# RedBoard_Plus.net
KiCad netlist of a schematic drawn in EAGLE
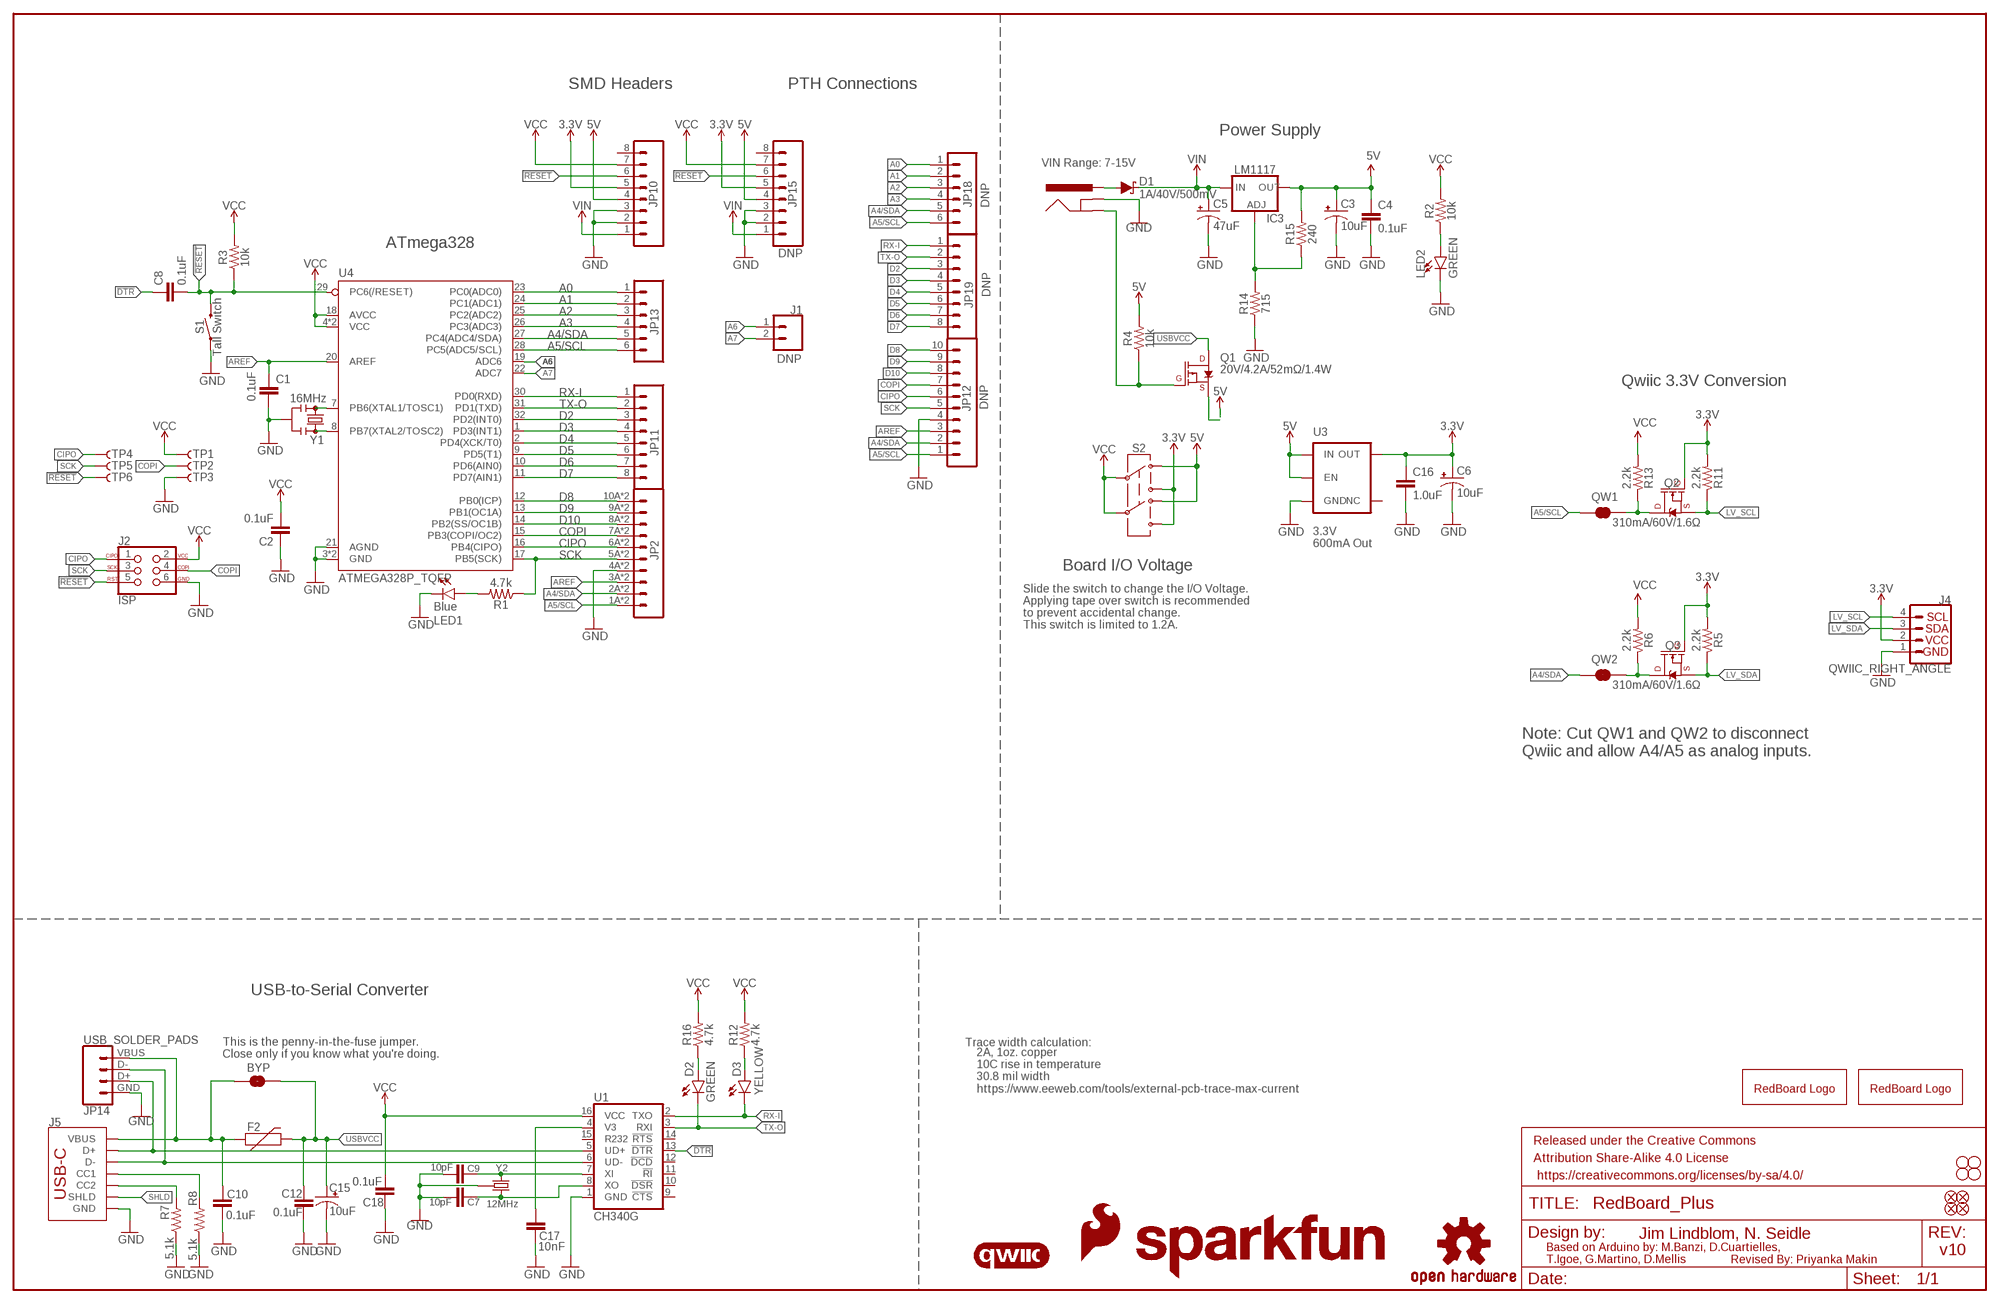
[diagram p0: schematic, sheet 1]

(export (version "E")
  (design (tool "Eeschema 10.0.6"))
  (components
    (comp (ref "BYP")
      (value "JUMPER-SMT_2_NO_SILK")
      (footprint "eagle-import:SMT-JUMPER_2_NO_SILK")
      (libsource (lib "eagle-import") (part "JUMPER-SMT_2_NO_SILK"))
    )
    (comp (ref "C1")
      (value "0.1uF")
      (footprint "eagle-import:0603")
      (libsource (lib "eagle-import") (part "0.1UF-0603-25V-(+80/-20%)"))
    )
    (comp (ref "C2")
      (value "0.1uF")
      (footprint "eagle-import:0603")
      (libsource (lib "eagle-import") (part "0.1UF-0603-25V-(+80/-20%)"))
    )
    (comp (ref "C3")
      (value "10uF")
      (footprint "eagle-import:EIA3216")
      (libsource (lib "eagle-import") (part "10UF-POLAR-EIA3216-16V-10%(TANT)"))
    )
    (comp (ref "C4")
      (value "0.1uF")
      (footprint "eagle-import:0603")
      (libsource (lib "eagle-import") (part "0.1UF-0603-25V-(+80/-20%)"))
    )
    (comp (ref "C5")
      (value "47uF")
      (footprint "eagle-import:PANASONIC_D")
      (libsource (lib "eagle-import") (part "47UF-POLAR-PANASONIC_D-35V-20%"))
    )
    (comp (ref "C6")
      (value "10uF")
      (footprint "eagle-import:EIA3216")
      (libsource (lib "eagle-import") (part "10UF-POLAR-EIA3216-16V-10%(TANT)"))
    )
    (comp (ref "C7")
      (value "10pF")
      (footprint "eagle-import:0603")
      (libsource (lib "eagle-import") (part "10PF-0603-50V-5%"))
    )
    (comp (ref "C8")
      (value "0.1uF")
      (footprint "eagle-import:0603")
      (libsource (lib "eagle-import") (part "0.1UF-0603-25V-(+80/-20%)"))
    )
    (comp (ref "C9")
      (value "10pF")
      (footprint "eagle-import:0603")
      (libsource (lib "eagle-import") (part "10PF-0603-50V-5%"))
    )
    (comp (ref "C10")
      (value "0.1uF")
      (footprint "eagle-import:0603")
      (libsource (lib "eagle-import") (part "0.1UF-0603-25V-(+80/-20%)"))
    )
    (comp (ref "C12")
      (value "0.1uF")
      (footprint "eagle-import:0603")
      (libsource (lib "eagle-import") (part "0.1UF-0603-25V-(+80/-20%)"))
    )
    (comp (ref "C15")
      (value "10uF")
      (footprint "eagle-import:EIA3216")
      (libsource (lib "eagle-import") (part "10UF-POLAR-EIA3216-16V-10%(TANT)"))
    )
    (comp (ref "C16")
      (value "1.0uF")
      (footprint "eagle-import:0603")
      (libsource (lib "eagle-import") (part "1.0UF-0603-16V-10%"))
    )
    (comp (ref "C17")
      (value "10nF")
      (footprint "eagle-import:0603")
      (libsource (lib "eagle-import") (part "10NF-0603-50V-10%"))
    )
    (comp (ref "C18")
      (value "0.1uF")
      (footprint "eagle-import:0603")
      (libsource (lib "eagle-import") (part "0.1UF-0603-25V-(+80/-20%)"))
    )
    (comp (ref "D1")
      (value "1A/40V/500mV")
      (footprint "eagle-import:SMA-DIODE")
      (libsource (lib "eagle-import") (part "DIODE-SCHOTTKY-SS14"))
    )
    (comp (ref "D2")
      (value "GREEN")
      (footprint "eagle-import:LED-1206")
      (libsource (lib "eagle-import") (part "LED-GREENLILYPAD"))
    )
    (comp (ref "D3")
      (value "YELLOW")
      (footprint "eagle-import:LED-1206-HIDDENSILK")
      (libsource (lib "eagle-import") (part "LED-YELLOW_HIDDENSILK"))
    )
    (comp (ref "F2")
      (value "6V/2A")
      (footprint "eagle-import:1210")
      (libsource (lib "eagle-import") (part "PPTC_6V2A"))
    )
    (comp (ref "FD1")
      (value "FIDUCIAL1X2")
      (footprint "eagle-import:FIDUCIAL-1X2")
      (libsource (lib "eagle-import") (part "FIDUCIAL1X2"))
    )
    (comp (ref "FD2")
      (value "FIDUCIAL1X2")
      (footprint "eagle-import:FIDUCIAL-1X2")
      (libsource (lib "eagle-import") (part "FIDUCIAL1X2"))
    )
    (comp (ref "FRAME1")
      (value "FRAME-LEDGER")
      (footprint "eagle-import:CREATIVE_COMMONS")
      (libsource (lib "eagle-import") (part "FRAME-LEDGER"))
    )
    (comp (ref "IC3")
      (value "LM1117")
      (footprint "eagle-import:SOT223")
      (fields (field (name "PROD_ID") "VREG-08170"))
      (libsource (lib "eagle-import") (part "V_REG_LM1117SOT223"))
    )
    (comp (ref "J1")
      (value "DNP")
      (footprint "eagle-import:1X02_NO_SILK")
      (libsource (lib "eagle-import") (part "CONN_021X02_NO_SILK"))
    )
    (comp (ref "J2")
      (value "ISP")
      (footprint "eagle-import:2X3_SMT_POSTS")
      (libsource (lib "eagle-import") (part "AVR_SPI_PROG_3X2SMD"))
    )
    (comp (ref "J3")
      (value "5.5x2.1mm Barrel")
      (footprint "eagle-import:POWER_JACK_SMD")
      (fields (field (name "PROD_ID") "CONN-08106"))
      (libsource (lib "eagle-import") (part "POWER_JACKSMD"))
    )
    (comp (ref "J4")
      (value "QWIIC_RIGHT_ANGLE")
      (footprint "eagle-import:JST04_1MM_RA")
      (libsource (lib "eagle-import") (part "QWIIC_CONNECTORJS-1MM"))
    )
    (comp (ref "J5")
      (value "USB Female Type C Connector")
      (footprint "eagle-import:USB-C-16P-2LAYER-PADS")
      (libsource (lib "eagle-import") (part "USB_C_2-LAYER_PADS"))
    )
    (comp (ref "JP1")
      (value "SFE_LOGO_NAME.1_INCH")
      (footprint "eagle-import:SFE_LOGO_NAME_.1")
      (libsource (lib "eagle-import") (part "SFE_LOGO_NAME.1_INCH"))
    )
    (comp (ref "JP2")
      (value "CONN_10SMD_COMBO-FEMALE")
      (footprint "eagle-import:1X10_SMD_COMBINED")
      (fields (field (name "PROD_ID") "CONN-11219"))
      (libsource (lib "eagle-import") (part "CONN_10SMD_COMBO-FEMALE"))
    )
    (comp (ref "JP3")
      (value "STAND-OFFTIGHT")
      (footprint "eagle-import:STAND-OFF-TIGHT")
      (libsource (lib "eagle-import") (part "STAND-OFFTIGHT"))
    )
    (comp (ref "JP4")
      (value "STAND-OFFTIGHT")
      (footprint "eagle-import:STAND-OFF-TIGHT")
      (libsource (lib "eagle-import") (part "STAND-OFFTIGHT"))
    )
    (comp (ref "JP5")
      (value "STAND-OFFTIGHT")
      (footprint "eagle-import:STAND-OFF-TIGHT")
      (libsource (lib "eagle-import") (part "STAND-OFFTIGHT"))
    )
    (comp (ref "JP6")
      (value "STAND-OFFTIGHT")
      (footprint "eagle-import:STAND-OFF-TIGHT")
      (libsource (lib "eagle-import") (part "STAND-OFFTIGHT"))
    )
    (comp (ref "JP7")
      (value "SFE_LOGO_FLAME.1_INCH")
      (footprint "eagle-import:SFE_LOGO_FLAME_.1")
      (libsource (lib "eagle-import") (part "SFE_LOGO_FLAME.1_INCH"))
    )
    (comp (ref "JP8")
      (value "FIDUCIAL1X2")
      (footprint "eagle-import:FIDUCIAL-1X2")
      (libsource (lib "eagle-import") (part "FIDUCIAL1X2"))
    )
    (comp (ref "JP9")
      (value "FIDUCIAL1X2")
      (footprint "eagle-import:FIDUCIAL-1X2")
      (libsource (lib "eagle-import") (part "FIDUCIAL1X2"))
    )
    (comp (ref "JP10")
      (value "CONN_08SMD-COMBO-FEMALE")
      (footprint "eagle-import:1X08_SMD_COMBINED")
      (fields (field (name "PROD_ID") "CONN-10204"))
      (libsource (lib "eagle-import") (part "CONN_08SMD-COMBO-FEMALE"))
    )
    (comp (ref "JP11")
      (value "JP11")
      (footprint "eagle-import:1X08_SMD_COMBINED")
      (fields (field (name "PROD_ID") "CONN-10204"))
      (libsource (lib "eagle-import") (part "CONN_08SMD-COMBO-FEMALE"))
    )
    (comp (ref "JP12")
      (value "DNP")
      (footprint "eagle-import:1X10_NO_SILK")
      (libsource (lib "eagle-import") (part "CONN_10NO_SILK_PTH_FEMALE"))
    )
    (comp (ref "JP13")
      (value "CONN_06SMD-STRAIGHT-COMBO-FEMALE")
      (footprint "eagle-import:1X06_SMD_STRAIGHT_COMBO")
      (fields (field (name "PROD_ID") "CONN-10203"))
      (libsource (lib "eagle-import") (part "CONN_06SMD-STRAIGHT-COMBO-FEMALE"))
    )
    (comp (ref "JP14")
      (value "USB_SOLDER_PADS")
      (footprint "eagle-import:USB-SOLDER-PADS")
      (libsource (lib "eagle-import") (part "USB_SOLDER_PADS"))
    )
    (comp (ref "JP15")
      (value "DNP")
      (footprint "eagle-import:1X08_NO_SILK")
      (libsource (lib "eagle-import") (part "CONN_08NO_SILK_DNP"))
    )
    (comp (ref "JP18")
      (value "DNP")
      (footprint "eagle-import:1X06_NO_SILK")
      (libsource (lib "eagle-import") (part "CONN_06NO_SILK_NO_POP"))
    )
    (comp (ref "JP19")
      (value "DNP")
      (footprint "eagle-import:1X08_NO_SILK")
      (libsource (lib "eagle-import") (part "CONN_08NO_SILK_DNP"))
    )
    (comp (ref "LED1")
      (value "Blue")
      (footprint "eagle-import:LED-1206-HIDDENSILK")
      (fields (field (name "PROD_ID") "DIO-09911"))
      (libsource (lib "eagle-import") (part "LED-BLUE_HIDDENSILK"))
    )
    (comp (ref "LED2")
      (value "GREEN")
      (footprint "eagle-import:LED-1206")
      (libsource (lib "eagle-import") (part "LED-GREENLILYPAD"))
    )
    (comp (ref "LOGO1")
      (value "QWIIC_LOGO_5MM")
      (footprint "eagle-import:QWIIC_5MM")
      (libsource (lib "eagle-import") (part "QWIIC_LOGO_5MM"))
    )
    (comp (ref "Q1")
      (value "20V/4.2A/52mΩ/1.4W")
      (footprint "eagle-import:SOT23-3")
      (libsource (lib "eagle-import") (part "MOSFET_PCH-DMG2305UX-7"))
    )
    (comp (ref "Q2")
      (value "310mA/60V/1.6Ω")
      (footprint "eagle-import:SOT323")
      (libsource (lib "eagle-import") (part "MOSFET-NCH-2N7002PW"))
    )
    (comp (ref "Q3")
      (value "310mA/60V/1.6Ω")
      (footprint "eagle-import:SOT323")
      (libsource (lib "eagle-import") (part "MOSFET-NCH-2N7002PW"))
    )
    (comp (ref "QW1")
      (value "JUMPER-SMT_2_NC_TRACE_SILK")
      (footprint "eagle-import:SMT-JUMPER_2_NC_TRACE_SILK")
      (libsource (lib "eagle-import") (part "JUMPER-SMT_2_NC_TRACE_SILK"))
    )
    (comp (ref "QW2")
      (value "JUMPER-SMT_2_NC_TRACE_SILK")
      (footprint "eagle-import:SMT-JUMPER_2_NC_TRACE_SILK")
      (libsource (lib "eagle-import") (part "JUMPER-SMT_2_NC_TRACE_SILK"))
    )
    (comp (ref "R1")
      (value "4.7k")
      (footprint "eagle-import:0603")
      (libsource (lib "eagle-import") (part "4.7KOHM-0603-1/10W-1%"))
    )
    (comp (ref "R2")
      (value "10k")
      (footprint "eagle-import:0603")
      (libsource (lib "eagle-import") (part "10KOHM-0603-1/10W-1%"))
    )
    (comp (ref "R3")
      (value "10k")
      (footprint "eagle-import:0603")
      (libsource (lib "eagle-import") (part "10KOHM-0603-1/10W-1%"))
    )
    (comp (ref "R4")
      (value "10k")
      (footprint "eagle-import:0603")
      (libsource (lib "eagle-import") (part "10KOHM-0603-1/10W-1%"))
    )
    (comp (ref "R5")
      (value "2.2k")
      (footprint "eagle-import:0603")
      (libsource (lib "eagle-import") (part "2.2KOHM-0603-1/10W-1%"))
    )
    (comp (ref "R6")
      (value "2.2k")
      (footprint "eagle-import:0603")
      (libsource (lib "eagle-import") (part "2.2KOHM-0603-1/10W-1%"))
    )
    (comp (ref "R7")
      (value "5.1k")
      (footprint "eagle-import:0603")
      (libsource (lib "eagle-import") (part "5.1KOHM5.1KOHM-0603-1/10W-1%"))
    )
    (comp (ref "R8")
      (value "5.1k")
      (footprint "eagle-import:0603")
      (libsource (lib "eagle-import") (part "5.1KOHM5.1KOHM-0603-1/10W-1%"))
    )
    (comp (ref "R11")
      (value "2.2k")
      (footprint "eagle-import:0603")
      (libsource (lib "eagle-import") (part "2.2KOHM-0603-1/10W-1%"))
    )
    (comp (ref "R12")
      (value "4.7k")
      (footprint "eagle-import:0603")
      (libsource (lib "eagle-import") (part "4.7KOHM-0603-1/10W-1%"))
    )
    (comp (ref "R13")
      (value "2.2k")
      (footprint "eagle-import:0603")
      (libsource (lib "eagle-import") (part "2.2KOHM-0603-1/10W-1%"))
    )
    (comp (ref "R14")
      (value "715")
      (footprint "eagle-import:0603")
      (libsource (lib "eagle-import") (part "715OHM-0603-1/10W-1%"))
    )
    (comp (ref "R15")
      (value "240")
      (footprint "eagle-import:0603")
      (libsource (lib "eagle-import") (part "240OHM-0603-1/10W-1%"))
    )
    (comp (ref "R16")
      (value "4.7k")
      (footprint "eagle-import:0603")
      (libsource (lib "eagle-import") (part "4.7KOHM-0603-1/10W-1%"))
    )
    (comp (ref "S1")
      (value "Tall Switch")
      (footprint "eagle-import:TACTILE_SWITCH_SMD_5.2MM")
      (libsource (lib "eagle-import") (part "MOMENTARY-SWITCH-SPST-SMD-5.2-TALL-REDUNDANT"))
    )
    (comp (ref "S2")
      (value "SWITCH-DPDT-SMD-AYZ0202")
      (footprint "eagle-import:SWITCH_DPDT_SMD_AYZ0202")
      (libsource (lib "eagle-import") (part "SWITCH-DPDT-SMD-AYZ0202"))
    )
    (comp (ref "TP1")
      (value "TP-3x5")
      (footprint "eagle-import:PAD.03X.05")
      (libsource (lib "eagle-import") (part "TEST-POINT3X5"))
    )
    (comp (ref "TP2")
      (value "TP-3x5")
      (footprint "eagle-import:PAD.03X.05")
      (libsource (lib "eagle-import") (part "TEST-POINT3X5"))
    )
    (comp (ref "TP3")
      (value "TP-3x5")
      (footprint "eagle-import:PAD.03X.05")
      (libsource (lib "eagle-import") (part "TEST-POINT3X5"))
    )
    (comp (ref "TP4")
      (value "TP-3x5")
      (footprint "eagle-import:PAD.03X.05")
      (libsource (lib "eagle-import") (part "TEST-POINT3X5"))
    )
    (comp (ref "TP5")
      (value "TP-3x5")
      (footprint "eagle-import:PAD.03X.05")
      (libsource (lib "eagle-import") (part "TEST-POINT3X5"))
    )
    (comp (ref "TP6")
      (value "TP-3x5")
      (footprint "eagle-import:PAD.03X.05")
      (libsource (lib "eagle-import") (part "TEST-POINT3X5"))
    )
    (comp (ref "U$1")
      (value "REDBOARD_LOGO")
      (footprint "eagle-import:REDBOARD_LOGO")
      (libsource (lib "eagle-import") (part "REDBOARD_LOGO"))
    )
    (comp (ref "U$3")
      (value "REDBOARD_LOGO")
      (footprint "eagle-import:REDBOARD_LOGO")
      (libsource (lib "eagle-import") (part "REDBOARD_LOGO"))
    )
    (comp (ref "U$16")
      (value "OSHW-LOGOS")
      (footprint "eagle-import:OSHW-LOGO-S")
      (libsource (lib "eagle-import") (part "OSHW-LOGOS"))
    )
    (comp (ref "U1")
      (value "CH340G")
      (footprint "eagle-import:SO016")
      (libsource (lib "eagle-import") (part "CH340GSMD"))
    )
    (comp (ref "U3")
      (value "3.3V")
      (footprint "eagle-import:SOT23-5")
      (libsource (lib "eagle-import") (part "V_REG_AP2112K-3.3V"))
    )
    (comp (ref "U4")
      (value "ATMEGA328P_TQFP")
      (footprint "eagle-import:TQFP32-08")
      (libsource (lib "eagle-import") (part "ATMEGA328P_TQFP"))
    )
    (comp (ref "Y1")
      (value "16MHz")
      (footprint "eagle-import:RESONATOR-SMD-3.2X1.3")
      (libsource (lib "eagle-import") (part "RESONATOR-16MHZSMD_3.2X1.3"))
    )
    (comp (ref "Y2")
      (value "12MHz")
      (footprint "eagle-import:CRYSTAL-SMD-3.2X2.5MM")
      (libsource (lib "eagle-import") (part "CRYSTAL-GROUNDEDSMD-3.2X2.5"))
    )
  )
  (nets
    (net (code "1") (name "/~{DTR}") (class "Default")
      (node (ref "C8") (pin "1") (pinfunction "1_1") (pintype "passive"))
      (node (ref "U1") (pin "13") (pinfunction "~{DTR}_13") (pintype "bidirectional"))
    )
    (net (code "2") (name "/~{RESET}") (class "Default")
      (node (ref "C8") (pin "2") (pinfunction "2_2") (pintype "passive"))
      (node (ref "J2") (pin "5") (pinfunction "5_5") (pintype "passive"))
      (node (ref "JP10") (pin "6") (pinfunction "6_6") (pintype "passive"))
      (node (ref "JP15") (pin "6") (pinfunction "6_6") (pintype "passive"))
      (node (ref "R3") (pin "1") (pinfunction "1_1") (pintype "passive"))
      (node (ref "S1") (pin "3") (pinfunction "2_3") (pintype "passive"))
      (node (ref "S1") (pin "4") (pinfunction "2_4") (pintype "passive"))
      (node (ref "TP6") (pin "P$1") (pinfunction "1_P$1") (pintype "bidirectional"))
      (node (ref "U4") (pin "29") (pinfunction "PC6(/RESET)_29") (pintype "bidirectional"))
    )
    (net (code "3") (name "3.3V") (class "Default")
      (node (ref "C16") (pin "1") (pinfunction "1_1") (pintype "passive"))
      (node (ref "C6") (pin "+") (pinfunction "+_+") (pintype "passive"))
      (node (ref "J4") (pin "2") (pinfunction "2_2") (pintype "power_in"))
      (node (ref "JP10") (pin "5") (pinfunction "5_5") (pintype "passive"))
      (node (ref "JP15") (pin "5") (pinfunction "5_5") (pintype "passive"))
      (node (ref "Q2") (pin "1") (pinfunction "G_1") (pintype "bidirectional"))
      (node (ref "Q3") (pin "1") (pinfunction "G_1") (pintype "bidirectional"))
      (node (ref "R11") (pin "2") (pinfunction "2_2") (pintype "passive"))
      (node (ref "R5") (pin "2") (pinfunction "2_2") (pintype "passive"))
      (node (ref "S2") (pin "1") (pinfunction "1_1") (pintype "bidirectional"))
      (node (ref "S2") (pin "4") (pinfunction "4_4") (pintype "bidirectional"))
      (node (ref "U3") (pin "5") (pinfunction "OUT_5") (pintype "passive"))
    )
    (net (code "4") (name "5V") (class "Default")
      (node (ref "C3") (pin "+") (pinfunction "+_+") (pintype "passive"))
      (node (ref "C4") (pin "1") (pinfunction "1_1") (pintype "passive"))
      (node (ref "IC3") (pin "2") (pinfunction "OUT_2") (pintype "output"))
      (node (ref "IC3") (pin "4") (pinfunction "OUT_4") (pintype "output"))
      (node (ref "JP10") (pin "4") (pinfunction "4_4") (pintype "passive"))
      (node (ref "JP15") (pin "4") (pinfunction "4_4") (pintype "passive"))
      (node (ref "Q1") (pin "2") (pinfunction "S_2") (pintype "bidirectional"))
      (node (ref "R15") (pin "2") (pinfunction "2_2") (pintype "passive"))
      (node (ref "R4") (pin "2") (pinfunction "2_2") (pintype "passive"))
      (node (ref "S2") (pin "3") (pinfunction "3_3") (pintype "bidirectional"))
      (node (ref "S2") (pin "6") (pinfunction "6_6") (pintype "bidirectional"))
      (node (ref "U3") (pin "1") (pinfunction "IN_1") (pintype "input"))
      (node (ref "U3") (pin "3") (pinfunction "EN_3") (pintype "input"))
    )
    (net (code "5") (name "A0") (class "Default")
      (node (ref "JP13") (pin "1") (pinfunction "1_1") (pintype "passive"))
      (node (ref "JP18") (pin "1") (pinfunction "1_1") (pintype "passive"))
      (node (ref "U4") (pin "23") (pinfunction "PC0(ADC0)_23") (pintype "bidirectional"))
    )
    (net (code "6") (name "A1") (class "Default")
      (node (ref "JP13") (pin "2") (pinfunction "2_2") (pintype "passive"))
      (node (ref "JP18") (pin "2") (pinfunction "2_2") (pintype "passive"))
      (node (ref "U4") (pin "24") (pinfunction "PC1(ADC1)_24") (pintype "bidirectional"))
    )
    (net (code "7") (name "A2") (class "Default")
      (node (ref "JP13") (pin "3") (pinfunction "3_3") (pintype "passive"))
      (node (ref "JP18") (pin "3") (pinfunction "3_3") (pintype "passive"))
      (node (ref "U4") (pin "25") (pinfunction "PC2(ADC2)_25") (pintype "bidirectional"))
    )
    (net (code "8") (name "A3") (class "Default")
      (node (ref "JP13") (pin "4") (pinfunction "4_4") (pintype "passive"))
      (node (ref "JP18") (pin "4") (pinfunction "4_4") (pintype "passive"))
      (node (ref "U4") (pin "26") (pinfunction "PC3(ADC3)_26") (pintype "bidirectional"))
    )
    (net (code "9") (name "A4{slash}SDA") (class "Default")
      (node (ref "JP12") (pin "2") (pinfunction "2_2") (pintype "passive"))
      (node (ref "JP13") (pin "5") (pinfunction "5_5") (pintype "passive"))
      (node (ref "JP18") (pin "5") (pinfunction "5_5") (pintype "passive"))
      (node (ref "JP2") (pin "2A") (pinfunction "2_2A") (pintype "passive"))
      (node (ref "JP2") (pin "2B") (pinfunction "2_2B") (pintype "passive"))
      (node (ref "QW2") (pin "1") (pinfunction "1_1") (pintype "passive"))
      (node (ref "U4") (pin "27") (pinfunction "PC4(ADC4/SDA)_27") (pintype "bidirectional"))
    )
    (net (code "10") (name "A5{slash}SCL") (class "Default")
      (node (ref "JP12") (pin "1") (pinfunction "1_1") (pintype "passive"))
      (node (ref "JP13") (pin "6") (pinfunction "6_6") (pintype "passive"))
      (node (ref "JP18") (pin "6") (pinfunction "6_6") (pintype "passive"))
      (node (ref "JP2") (pin "1A") (pinfunction "1_1A") (pintype "passive"))
      (node (ref "JP2") (pin "1B") (pinfunction "1_1B") (pintype "passive"))
      (node (ref "QW1") (pin "1") (pinfunction "1_1") (pintype "passive"))
      (node (ref "U4") (pin "28") (pinfunction "PC5(ADC5/SCL)_28") (pintype "bidirectional"))
    )
    (net (code "11") (name "A6") (class "Default")
      (node (ref "J1") (pin "1") (pinfunction "1_1") (pintype "passive"))
      (node (ref "U4") (pin "19") (pinfunction "ADC6_19") (pintype "bidirectional"))
    )
    (net (code "12") (name "A7") (class "Default")
      (node (ref "J1") (pin "2") (pinfunction "2_2") (pintype "passive"))
      (node (ref "U4") (pin "22") (pinfunction "ADC7_22") (pintype "bidirectional"))
    )
    (net (code "13") (name "AREF") (class "Default")
      (node (ref "C1") (pin "1") (pinfunction "1_1") (pintype "passive"))
      (node (ref "JP12") (pin "3") (pinfunction "3_3") (pintype "passive"))
      (node (ref "JP2") (pin "3A") (pinfunction "3_3A") (pintype "passive"))
      (node (ref "JP2") (pin "3B") (pinfunction "3_3B") (pintype "passive"))
      (node (ref "U4") (pin "20") (pinfunction "AREF_20") (pintype "bidirectional"))
    )
    (net (code "14") (name "CIPO") (class "Default")
      (node (ref "J2") (pin "1") (pinfunction "1_1") (pintype "passive"))
      (node (ref "JP12") (pin "6") (pinfunction "6_6") (pintype "passive"))
      (node (ref "JP2") (pin "6A") (pinfunction "6_6A") (pintype "passive"))
      (node (ref "JP2") (pin "6B") (pinfunction "6_6B") (pintype "passive"))
      (node (ref "TP4") (pin "P$1") (pinfunction "1_P$1") (pintype "bidirectional"))
      (node (ref "U4") (pin "16") (pinfunction "PB4(CIPO)_16") (pintype "bidirectional"))
    )
    (net (code "15") (name "COPI") (class "Default")
      (node (ref "J2") (pin "4") (pinfunction "4_4") (pintype "passive"))
      (node (ref "JP12") (pin "7") (pinfunction "7_7") (pintype "passive"))
      (node (ref "JP2") (pin "7A") (pinfunction "7_7A") (pintype "passive"))
      (node (ref "JP2") (pin "7B") (pinfunction "7_7B") (pintype "passive"))
      (node (ref "TP2") (pin "P$1") (pinfunction "1_P$1") (pintype "bidirectional"))
      (node (ref "U4") (pin "15") (pinfunction "PB3(COPI/OC2)_15") (pintype "bidirectional"))
    )
    (net (code "16") (name "D2") (class "Default")
      (node (ref "JP11") (pin "3") (pinfunction "3_3") (pintype "passive"))
      (node (ref "JP19") (pin "3") (pinfunction "3_3") (pintype "passive"))
      (node (ref "U4") (pin "32") (pinfunction "PD2(INT0)_32") (pintype "bidirectional"))
    )
    (net (code "17") (name "D3") (class "Default")
      (node (ref "JP11") (pin "4") (pinfunction "4_4") (pintype "passive"))
      (node (ref "JP19") (pin "4") (pinfunction "4_4") (pintype "passive"))
      (node (ref "U4") (pin "1") (pinfunction "PD3(INT1)_1") (pintype "bidirectional"))
    )
    (net (code "18") (name "D4") (class "Default")
      (node (ref "JP11") (pin "5") (pinfunction "5_5") (pintype "passive"))
      (node (ref "JP19") (pin "5") (pinfunction "5_5") (pintype "passive"))
      (node (ref "U4") (pin "2") (pinfunction "PD4(XCK/T0)_2") (pintype "bidirectional"))
    )
    (net (code "19") (name "D5") (class "Default")
      (node (ref "JP11") (pin "6") (pinfunction "6_6") (pintype "passive"))
      (node (ref "JP19") (pin "6") (pinfunction "6_6") (pintype "passive"))
      (node (ref "U4") (pin "9") (pinfunction "PD5(T1)_9") (pintype "bidirectional"))
    )
    (net (code "20") (name "D6") (class "Default")
      (node (ref "JP11") (pin "7") (pinfunction "7_7") (pintype "passive"))
      (node (ref "JP19") (pin "7") (pinfunction "7_7") (pintype "passive"))
      (node (ref "U4") (pin "10") (pinfunction "PD6(AIN0)_10") (pintype "bidirectional"))
    )
    (net (code "21") (name "D7") (class "Default")
      (node (ref "JP11") (pin "8") (pinfunction "8_8") (pintype "passive"))
      (node (ref "JP19") (pin "8") (pinfunction "8_8") (pintype "passive"))
      (node (ref "U4") (pin "11") (pinfunction "PD7(AIN1)_11") (pintype "bidirectional"))
    )
    (net (code "22") (name "D8") (class "Default")
      (node (ref "JP12") (pin "10") (pinfunction "10_10") (pintype "passive"))
      (node (ref "JP2") (pin "10A") (pinfunction "10_10A") (pintype "passive"))
      (node (ref "JP2") (pin "10B") (pinfunction "10_10B") (pintype "passive"))
      (node (ref "U4") (pin "12") (pinfunction "PB0(ICP)_12") (pintype "bidirectional"))
    )
    (net (code "23") (name "D9") (class "Default")
      (node (ref "JP12") (pin "9") (pinfunction "9_9") (pintype "passive"))
      (node (ref "JP2") (pin "9A") (pinfunction "9_9A") (pintype "passive"))
      (node (ref "JP2") (pin "9B") (pinfunction "9_9B") (pintype "passive"))
      (node (ref "U4") (pin "13") (pinfunction "PB1(OC1A)_13") (pintype "bidirectional"))
    )
    (net (code "24") (name "D10") (class "Default")
      (node (ref "JP12") (pin "8") (pinfunction "8_8") (pintype "passive"))
      (node (ref "JP2") (pin "8A") (pinfunction "8_8A") (pintype "passive"))
      (node (ref "JP2") (pin "8B") (pinfunction "8_8B") (pintype "passive"))
      (node (ref "U4") (pin "14") (pinfunction "PB2(SS/OC1B)_14") (pintype "bidirectional"))
    )
    (net (code "25") (name "GND") (class "Default")
      (node (ref "C1") (pin "2") (pinfunction "2_2") (pintype "passive"))
      (node (ref "C10") (pin "2") (pinfunction "2_2") (pintype "passive"))
      (node (ref "C12") (pin "2") (pinfunction "2_2") (pintype "passive"))
      (node (ref "C15") (pin "-") (pinfunction "-_-") (pintype "passive"))
      (node (ref "C16") (pin "2") (pinfunction "2_2") (pintype "passive"))
      (node (ref "C17") (pin "2") (pinfunction "2_2") (pintype "passive"))
      (node (ref "C18") (pin "2") (pinfunction "2_2") (pintype "passive"))
      (node (ref "C2") (pin "1") (pinfunction "1_1") (pintype "passive"))
      (node (ref "C3") (pin "-") (pinfunction "-_-") (pintype "passive"))
      (node (ref "C4") (pin "2") (pinfunction "2_2") (pintype "passive"))
      (node (ref "C5") (pin "-") (pinfunction "-_-") (pintype "passive"))
      (node (ref "C6") (pin "-") (pinfunction "-_-") (pintype "passive"))
      (node (ref "C7") (pin "2") (pinfunction "2_2") (pintype "passive"))
      (node (ref "C9") (pin "2") (pinfunction "2_2") (pintype "passive"))
      (node (ref "J2") (pin "6") (pinfunction "6_6") (pintype "passive"))
      (node (ref "J3") (pin "GND") (pinfunction "GNDBREAK_GND") (pintype "bidirectional"))
      (node (ref "J4") (pin "1") (pinfunction "1_1") (pintype "power_in"))
      (node (ref "J5") (pin "GND") (pinfunction "GND_GND") (pintype "bidirectional"))
      (node (ref "J5") (pin "GND2") (pinfunction "GND_GND2") (pintype "bidirectional"))
      (node (ref "JP10") (pin "2") (pinfunction "2_2") (pintype "passive"))
      (node (ref "JP10") (pin "3") (pinfunction "3_3") (pintype "passive"))
      (node (ref "JP12") (pin "4") (pinfunction "4_4") (pintype "passive"))
      (node (ref "JP14") (pin "GND") (pinfunction "4_GND") (pintype "passive"))
      (node (ref "JP15") (pin "2") (pinfunction "2_2") (pintype "passive"))
      (node (ref "JP15") (pin "3") (pinfunction "3_3") (pintype "passive"))
      (node (ref "JP2") (pin "4A") (pinfunction "4_4A") (pintype "passive"))
      (node (ref "JP2") (pin "4B") (pinfunction "4_4B") (pintype "passive"))
      (node (ref "LED1") (pin "C") (pinfunction "C_C") (pintype "passive"))
      (node (ref "LED2") (pin "C") (pinfunction "C_C") (pintype "passive"))
      (node (ref "R14") (pin "1") (pinfunction "1_1") (pintype "passive"))
      (node (ref "R7") (pin "1") (pinfunction "1_1") (pintype "passive"))
      (node (ref "R8") (pin "1") (pinfunction "1_1") (pintype "passive"))
      (node (ref "S1") (pin "1") (pinfunction "1_1") (pintype "passive"))
      (node (ref "S1") (pin "2") (pinfunction "1_2") (pintype "passive"))
      (node (ref "TP3") (pin "P$1") (pinfunction "1_P$1") (pintype "bidirectional"))
      (node (ref "U1") (pin "1") (pinfunction "GND_1") (pintype "bidirectional"))
      (node (ref "U3") (pin "2") (pinfunction "GND_2") (pintype "input"))
      (node (ref "U4") (pin "21") (pinfunction "AGND_21") (pintype "bidirectional"))
      (node (ref "U4") (pin "3") (pinfunction "GND_3") (pintype "bidirectional"))
      (node (ref "U4") (pin "5") (pinfunction "GND_5") (pintype "bidirectional"))
      (node (ref "Y1") (pin "2") (pinfunction "2_2") (pintype "passive"))
      (node (ref "Y2") (pin "2") (pinfunction "GND_2") (pintype "power_in"))
      (node (ref "Y2") (pin "4") (pinfunction "GND_4") (pintype "power_in"))
    )
    (net (code "26") (name "LV_SCL") (class "Default")
      (node (ref "J4") (pin "4") (pinfunction "4_4") (pintype "passive"))
      (node (ref "Q2") (pin "2") (pinfunction "S_2") (pintype "bidirectional"))
      (node (ref "R11") (pin "1") (pinfunction "1_1") (pintype "passive"))
    )
    (net (code "27") (name "LV_SDA") (class "Default")
      (node (ref "J4") (pin "3") (pinfunction "3_3") (pintype "passive"))
      (node (ref "Q3") (pin "2") (pinfunction "S_2") (pintype "bidirectional"))
      (node (ref "R5") (pin "1") (pinfunction "1_1") (pintype "passive"))
    )
    (net (code "28") (name "Net-(D2-PadA)") (class "Default")
      (node (ref "D2") (pin "A") (pinfunction "A_A") (pintype "passive"))
      (node (ref "R16") (pin "1") (pinfunction "1_1") (pintype "passive"))
    )
    (net (code "29") (name "Net-(D3-PadA)") (class "Default")
      (node (ref "D3") (pin "A") (pinfunction "A_A") (pintype "passive"))
      (node (ref "R12") (pin "1") (pinfunction "1_1") (pintype "passive"))
    )
    (net (code "30") (name "Net-(IC3-ADJ)") (class "Default")
      (node (ref "IC3") (pin "1") (pinfunction "ADJ_1") (pintype "input"))
      (node (ref "R14") (pin "2") (pinfunction "2_2") (pintype "passive"))
      (node (ref "R15") (pin "1") (pinfunction "1_1") (pintype "passive"))
    )
    (net (code "31") (name "Net-(J3-GND)") (class "Default")
      (node (ref "J3") (pin "P$4") (pinfunction "GND_P$4") (pintype "bidirectional"))
      (node (ref "Q1") (pin "1") (pinfunction "G_1") (pintype "bidirectional"))
      (node (ref "R4") (pin "1") (pinfunction "1_1") (pintype "passive"))
    )
    (net (code "32") (name "Net-(J3-PWR)") (class "Default")
      (node (ref "D1") (pin "A") (pinfunction "A_A") (pintype "passive"))
      (node (ref "J3") (pin "VIN0") (pinfunction "PWR_VIN0") (pintype "bidirectional"))
    )
    (net (code "33") (name "Net-(J5-CC1)") (class "Default")
      (node (ref "J5") (pin "A5") (pinfunction "CC1_A5") (pintype "bidirectional"))
      (node (ref "R8") (pin "2") (pinfunction "2_2") (pintype "passive"))
    )
    (net (code "34") (name "Net-(J5-CC2)") (class "Default")
      (node (ref "J5") (pin "B5") (pinfunction "CC2_B5") (pintype "bidirectional"))
      (node (ref "R7") (pin "2") (pinfunction "2_2") (pintype "passive"))
    )
    (net (code "35") (name "Net-(JP14-1)") (class "Default")
      (node (ref "BYP") (pin "1") (pinfunction "1_1") (pintype "passive"))
      (node (ref "C10") (pin "1") (pinfunction "1_1") (pintype "passive"))
      (node (ref "F2") (pin "1") (pinfunction "1_1") (pintype "bidirectional"))
      (node (ref "J5") (pin "VBUS1") (pinfunction "VBUS_VBUS1") (pintype "bidirectional"))
      (node (ref "J5") (pin "VBUS2") (pinfunction "VBUS_VBUS2") (pintype "bidirectional"))
      (node (ref "JP14") (pin "VBUS") (pinfunction "1_VBUS") (pintype "passive"))
    )
    (net (code "36") (name "Net-(JP14-2)") (class "Default")
      (node (ref "J5") (pin "A7") (pinfunction "D-_A7") (pintype "bidirectional"))
      (node (ref "J5") (pin "B7") (pinfunction "D-_B7") (pintype "bidirectional"))
      (node (ref "JP14") (pin "D-") (pinfunction "2_D-") (pintype "passive"))
      (node (ref "U1") (pin "6") (pinfunction "UD-_6") (pintype "bidirectional"))
    )
    (net (code "37") (name "Net-(JP14-3)") (class "Default")
      (node (ref "J5") (pin "A6") (pinfunction "D+_A6") (pintype "bidirectional"))
      (node (ref "J5") (pin "B6") (pinfunction "D+_B6") (pintype "bidirectional"))
      (node (ref "JP14") (pin "D+") (pinfunction "3_D+") (pintype "passive"))
      (node (ref "U1") (pin "5") (pinfunction "UD+_5") (pintype "bidirectional"))
    )
    (net (code "38") (name "Net-(LED1-PadA)") (class "Default")
      (node (ref "LED1") (pin "A") (pinfunction "A_A") (pintype "passive"))
      (node (ref "R1") (pin "2") (pinfunction "2_2") (pintype "passive"))
    )
    (net (code "39") (name "Net-(LED2-PadA)") (class "Default")
      (node (ref "LED2") (pin "A") (pinfunction "A_A") (pintype "passive"))
      (node (ref "R2") (pin "1") (pinfunction "1_1") (pintype "passive"))
    )
    (net (code "40") (name "Net-(Q2-D)") (class "Default")
      (node (ref "Q2") (pin "3") (pinfunction "D_3") (pintype "bidirectional"))
      (node (ref "QW1") (pin "2") (pinfunction "2_2") (pintype "passive"))
      (node (ref "R13") (pin "1") (pinfunction "1_1") (pintype "passive"))
    )
    (net (code "41") (name "Net-(Q3-D)") (class "Default")
      (node (ref "Q3") (pin "3") (pinfunction "D_3") (pintype "bidirectional"))
      (node (ref "QW2") (pin "2") (pinfunction "2_2") (pintype "passive"))
      (node (ref "R6") (pin "1") (pinfunction "1_1") (pintype "passive"))
    )
    (net (code "42") (name "Net-(U1-V3)") (class "Default")
      (node (ref "C17") (pin "1") (pinfunction "1_1") (pintype "passive"))
      (node (ref "U1") (pin "4") (pinfunction "V3_4") (pintype "bidirectional"))
    )
    (net (code "43") (name "Net-(U1-XI)") (class "Default")
      (node (ref "C9") (pin "1") (pinfunction "1_1") (pintype "passive"))
      (node (ref "U1") (pin "7") (pinfunction "XI_7") (pintype "bidirectional"))
      (node (ref "Y2") (pin "1") (pinfunction "1_1") (pintype "passive"))
    )
    (net (code "44") (name "Net-(U1-XO)") (class "Default")
      (node (ref "C7") (pin "1") (pinfunction "1_1") (pintype "passive"))
      (node (ref "U1") (pin "8") (pinfunction "XO_8") (pintype "bidirectional"))
      (node (ref "Y2") (pin "3") (pinfunction "2_3") (pintype "passive"))
    )
    (net (code "45") (name "Net-(U4-PB6(XTAL1{slash}TOSC1))") (class "Default")
      (node (ref "U4") (pin "7") (pinfunction "PB6(XTAL1/TOSC1)_7") (pintype "bidirectional"))
      (node (ref "Y1") (pin "1") (pinfunction "1_1") (pintype "passive"))
    )
    (net (code "46") (name "Net-(U4-PB7(XTAL2{slash}TOSC2))") (class "Default")
      (node (ref "U4") (pin "8") (pinfunction "PB7(XTAL2/TOSC2)_8") (pintype "bidirectional"))
      (node (ref "Y1") (pin "3") (pinfunction "3_3") (pintype "passive"))
    )
    (net (code "47") (name "RX-I") (class "Default")
      (node (ref "D3") (pin "C") (pinfunction "C_C") (pintype "passive"))
      (node (ref "JP11") (pin "1") (pinfunction "1_1") (pintype "passive"))
      (node (ref "JP19") (pin "1") (pinfunction "1_1") (pintype "passive"))
      (node (ref "U1") (pin "2") (pinfunction "TXO_2") (pintype "bidirectional"))
      (node (ref "U4") (pin "30") (pinfunction "PD0(RXD)_30") (pintype "bidirectional"))
    )
    (net (code "48") (name "SCK") (class "Default")
      (node (ref "J2") (pin "3") (pinfunction "3_3") (pintype "passive"))
      (node (ref "JP12") (pin "5") (pinfunction "5_5") (pintype "passive"))
      (node (ref "JP2") (pin "5A") (pinfunction "5_5A") (pintype "passive"))
      (node (ref "JP2") (pin "5B") (pinfunction "5_5B") (pintype "passive"))
      (node (ref "R1") (pin "1") (pinfunction "1_1") (pintype "passive"))
      (node (ref "TP5") (pin "P$1") (pinfunction "1_P$1") (pintype "bidirectional"))
      (node (ref "U4") (pin "17") (pinfunction "PB5(SCK)_17") (pintype "bidirectional"))
    )
    (net (code "49") (name "SHLD") (class "Default")
      (node (ref "J5") (pin "SHLD1") (pinfunction "SHLD_SHLD1") (pintype "bidirectional"))
      (node (ref "J5") (pin "SHLD2") (pinfunction "SHLD_SHLD2") (pintype "bidirectional"))
      (node (ref "J5") (pin "SHLD3") (pinfunction "SHLD_SHLD3") (pintype "bidirectional"))
      (node (ref "J5") (pin "SHLD4") (pinfunction "SHLD_SHLD4") (pintype "bidirectional"))
    )
    (net (code "50") (name "TX-O") (class "Default")
      (node (ref "D2") (pin "C") (pinfunction "C_C") (pintype "passive"))
      (node (ref "JP11") (pin "2") (pinfunction "2_2") (pintype "passive"))
      (node (ref "JP19") (pin "2") (pinfunction "2_2") (pintype "passive"))
      (node (ref "U1") (pin "3") (pinfunction "RXI_3") (pintype "bidirectional"))
      (node (ref "U4") (pin "31") (pinfunction "PD1(TXD)_31") (pintype "bidirectional"))
    )
    (net (code "51") (name "USBVCC") (class "Default")
      (node (ref "BYP") (pin "2") (pinfunction "2_2") (pintype "passive"))
      (node (ref "C12") (pin "1") (pinfunction "1_1") (pintype "passive"))
      (node (ref "C15") (pin "+") (pinfunction "+_+") (pintype "passive"))
      (node (ref "F2") (pin "2") (pinfunction "2_2") (pintype "bidirectional"))
      (node (ref "Q1") (pin "3") (pinfunction "D_3") (pintype "bidirectional"))
    )
    (net (code "52") (name "VCC") (class "Default")
      (node (ref "C18") (pin "1") (pinfunction "1_1") (pintype "passive"))
      (node (ref "C2") (pin "2") (pinfunction "2_2") (pintype "passive"))
      (node (ref "J2") (pin "2") (pinfunction "2_2") (pintype "passive"))
      (node (ref "JP10") (pin "7") (pinfunction "7_7") (pintype "passive"))
      (node (ref "JP15") (pin "7") (pinfunction "7_7") (pintype "passive"))
      (node (ref "R12") (pin "2") (pinfunction "2_2") (pintype "passive"))
      (node (ref "R13") (pin "2") (pinfunction "2_2") (pintype "passive"))
      (node (ref "R16") (pin "2") (pinfunction "2_2") (pintype "passive"))
      (node (ref "R2") (pin "2") (pinfunction "2_2") (pintype "passive"))
      (node (ref "R3") (pin "2") (pinfunction "2_2") (pintype "passive"))
      (node (ref "R6") (pin "2") (pinfunction "2_2") (pintype "passive"))
      (node (ref "S2") (pin "2") (pinfunction "2_2") (pintype "bidirectional"))
      (node (ref "S2") (pin "5") (pinfunction "5_5") (pintype "bidirectional"))
      (node (ref "TP1") (pin "P$1") (pinfunction "1_P$1") (pintype "bidirectional"))
      (node (ref "U1") (pin "16") (pinfunction "VCC_16") (pintype "bidirectional"))
      (node (ref "U4") (pin "18") (pinfunction "AVCC_18") (pintype "bidirectional"))
      (node (ref "U4") (pin "4") (pinfunction "VCC_4") (pintype "bidirectional"))
      (node (ref "U4") (pin "6") (pinfunction "VCC_6") (pintype "bidirectional"))
    )
    (net (code "53") (name "VIN") (class "Default")
      (node (ref "C5") (pin "+") (pinfunction "+_+") (pintype "passive"))
      (node (ref "D1") (pin "C") (pinfunction "C_C") (pintype "passive"))
      (node (ref "IC3") (pin "3") (pinfunction "IN_3") (pintype "input"))
      (node (ref "JP10") (pin "1") (pinfunction "1_1") (pintype "passive"))
      (node (ref "JP15") (pin "1") (pinfunction "1_1") (pintype "passive"))
    )
    (net (code "54") (name "unconnected-(JP10-Pad8)") (class "Default")
      (node (ref "JP10") (pin "8") (pinfunction "8_8") (pintype "passive"))
    )
    (net (code "55") (name "unconnected-(JP15-Pad8)") (class "Default")
      (node (ref "JP15") (pin "8") (pinfunction "8_8") (pintype "passive"))
    )
    (net (code "56") (name "unconnected-(U1-R232-Pad15)") (class "Default")
      (node (ref "U1") (pin "15") (pinfunction "R232_15") (pintype "bidirectional"))
    )
    (net (code "57") (name "unconnected-(U1-~{CTS}-Pad9)") (class "Default")
      (node (ref "U1") (pin "9") (pinfunction "~{CTS}_9") (pintype "bidirectional"))
    )
    (net (code "58") (name "unconnected-(U1-~{DCD}-Pad12)") (class "Default")
      (node (ref "U1") (pin "12") (pinfunction "~{DCD}_12") (pintype "bidirectional"))
    )
    (net (code "59") (name "unconnected-(U1-~{DSR}-Pad10)") (class "Default")
      (node (ref "U1") (pin "10") (pinfunction "~{DSR}_10") (pintype "bidirectional"))
    )
    (net (code "60") (name "unconnected-(U1-~{RI}-Pad11)") (class "Default")
      (node (ref "U1") (pin "11") (pinfunction "~{RI}_11") (pintype "bidirectional"))
    )
    (net (code "61") (name "unconnected-(U1-~{RTS}-Pad14)") (class "Default")
      (node (ref "U1") (pin "14") (pinfunction "~{RTS}_14") (pintype "bidirectional"))
    )
    (net (code "62") (name "unconnected-(U3-NC-Pad4)") (class "Default")
      (node (ref "U3") (pin "4") (pinfunction "NC_4") (pintype "no_connect"))
    )
  )
)
